# HV-Measurement.net
KiCad netlist of a schematic drawn in Altium Designer
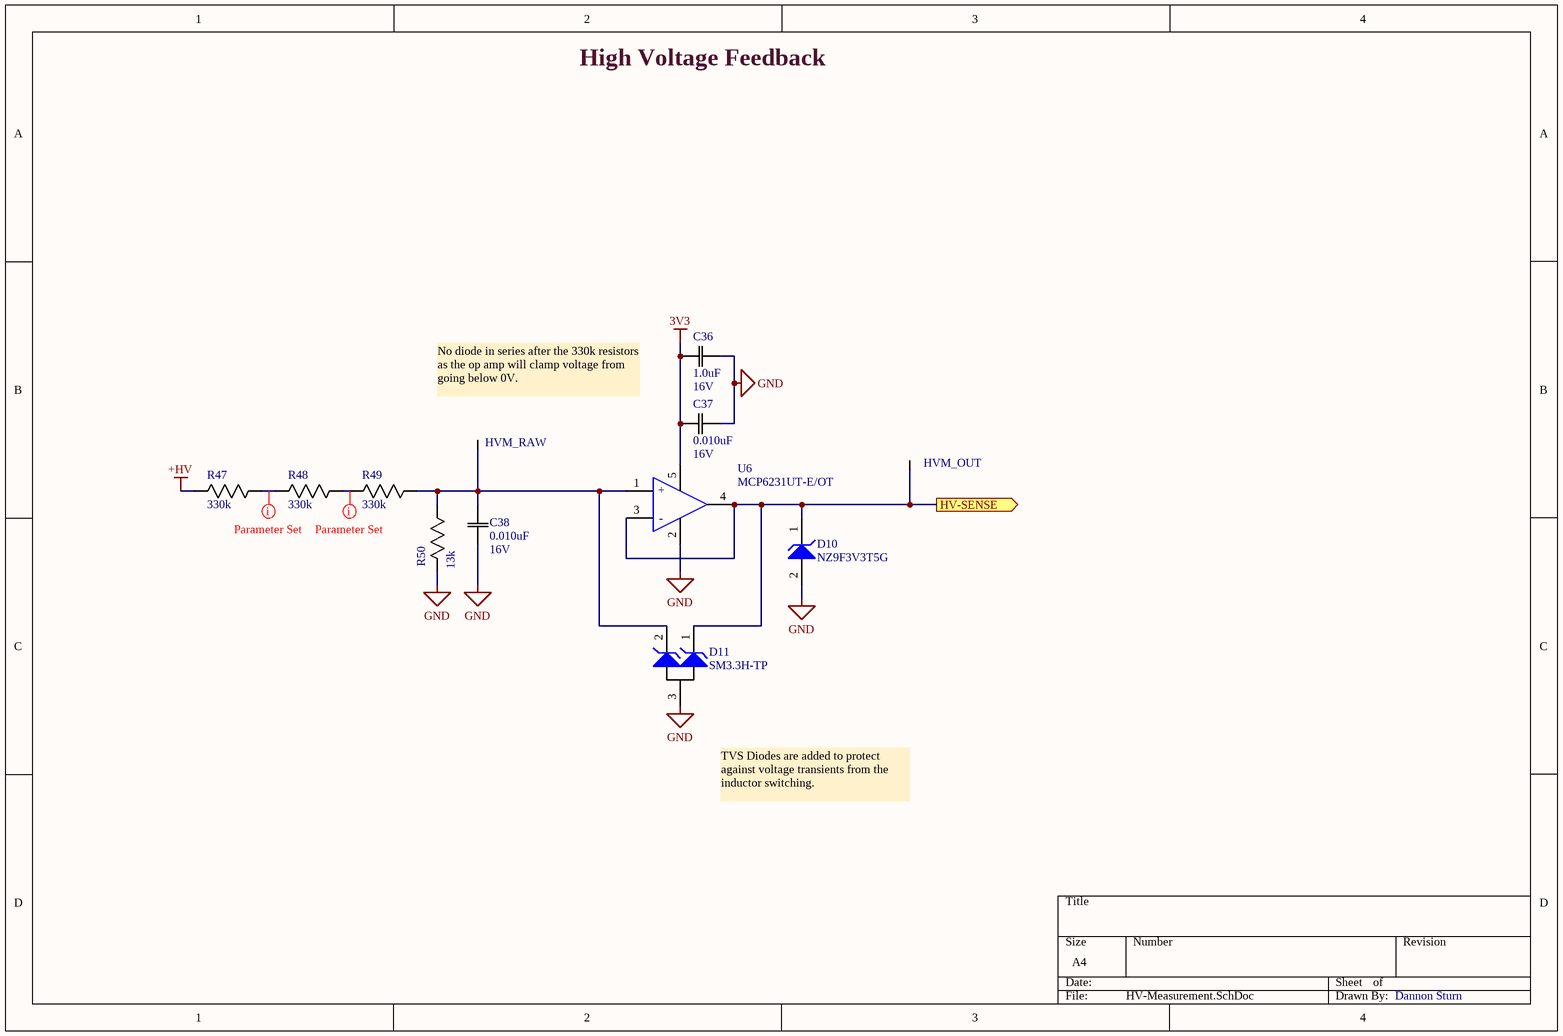
[diagram p0: HV-Measurement.SchDoc]

(export (version "E")
  (design (tool "Eeschema 10.0.6"))
  (components
    (comp (ref "C36")
      (value "1.0uF")
      (footprint "0603")
      (description "CAP CER 1.0UF 16V X5R 0603/0805")
      (fields
        (field (name "TOLERANCE") "10%")
        (field (name "RATING") "16V")
        (field (name "PART NUMBER") "CAP 1.0uF 16V")
      )
      (libsource (lib "capacitor_library") (part "CAP 1.0uF 16V"))
    )
    (comp (ref "C37")
      (value "0.010uF")
      (footprint "0603")
      (description "CAP CER 0.010UF 16V X5R 0603")
      (fields
        (field (name "TOLERANCE") "10%")
        (field (name "RATING") "16V")
        (field (name "PART NUMBER") "CAP 0.010uF 16V")
      )
      (libsource (lib "capacitor_library") (part "CAP 0.010uF 16V"))
    )
    (comp (ref "C38")
      (value "0.010uF")
      (footprint "0603")
      (description "CAP CER 0.010UF 16V X5R 0603")
      (fields
        (field (name "TOLERANCE") "10%")
        (field (name "RATING") "16V")
        (field (name "PART NUMBER") "CAP 0.010uF 16V")
      )
      (libsource (lib "capacitor_library") (part "CAP 0.010uF 16V"))
    )
    (comp (ref "D10")
      (value "NZ9F3V3T5G")
      (footprint "SOD-923_0P6X0P85_ONS")
      (description "Zener Diode 3.3 V 200 mW ±5% Surface Mount SOD-923")
      (fields
        (field (name "PART NUMBER") "DIODE ZENER 3.3 200mW")
        (field (name "COPYRIGHT") "Copyright (C) 2021 Ultra Librarian. All rights reserved.")
      )
      (libsource (lib "Diode_Library") (part "DIODE ZENER 3.3 200mW"))
    )
    (comp (ref "D11")
      (value "SM3.3H-TP")
      (footprint "SOT-23A-3")
      (description "3.3V Reverese Standoff, 3.5V Breakdown, 12.5V Clamp 40A (8/20µs) Ipp Tvs Diode SMD SOT-23")
      (fields (field (name "PART NUMBER") "DIODE TVS 3.3VR 3.5VBR"))
      (libsource (lib "Diode_Library") (part "DIODE TVS 3.3VR 3.5VBR"))
    )
    (comp (ref "HVM_OUT")
      (value "Test Point (Via)")
      (footprint "TP")
      (libsource (lib "IC_Library") (part "Test Point (Via)"))
    )
    (comp (ref "HVM_RAW")
      (value "Test Point (Via)")
      (footprint "TP")
      (libsource (lib "IC_Library") (part "Test Point (Via)"))
    )
    (comp (ref "R47")
      (value "330k")
      (footprint "0603")
      (description "RES SMD 274K OHM 1% 1/8W 0603")
      (fields (field (name "PART NUMBER") "RES 330k 1/8W - 1%"))
      (libsource (lib "Resistor_Library") (part "RES 330k 1/8W - 1%"))
    )
    (comp (ref "R48")
      (value "330k")
      (footprint "0603")
      (description "RES SMD 274K OHM 1% 1/8W 0603")
      (fields (field (name "PART NUMBER") "RES 330k 1/8W - 1%"))
      (libsource (lib "Resistor_Library") (part "RES 330k 1/8W - 1%"))
    )
    (comp (ref "R49")
      (value "330k")
      (footprint "0603")
      (description "RES SMD 274K OHM 1% 1/8W 0603")
      (fields (field (name "PART NUMBER") "RES 330k 1/8W - 1%"))
      (libsource (lib "Resistor_Library") (part "RES 330k 1/8W - 1%"))
    )
    (comp (ref "R50")
      (value "13k")
      (footprint "0603")
      (description "RES SMD 13K OHM 5% 1/8W 0603")
      (fields (field (name "TOLERANCE") "5%") (field (name "PART NUMBER") "RES 13k 1/8W"))
      (libsource (lib "Resistor_Library") (part "RES 13k 1/8W"))
    )
    (comp (ref "U6")
      (value "MCP6231UT-E/OT")
      (footprint "SOT-23-5_MC_MCH-L")
      (fields
        (field (name "PART NUMBER") "OP AMP MCP6231UT-E_OT")
        (field (name "COPYRIGHT") "Copyright (C) 2021 Ultra Librarian. All rights reserved.")
      )
      (libsource (lib "IC_Library") (part "OP AMP MCP6231UT-E/OT"))
    )
  )
  (nets
    (net (code "1") (name "+HV") (class "Default")
      (node (ref "R47") (pin "2") (pinfunction "R2_2") (pintype "passive"))
    )
    (net (code "2") (name "/HV-SENSE") (class "Default")
      (node (ref "D10") (pin "1") (pinfunction "K_1") (pintype "passive"))
      (node (ref "D11") (pin "1") (pinfunction "1_1") (pintype "passive"))
      (node (ref "HVM_OUT") (pin "1") (pinfunction "1_1") (pintype "passive"))
      (node (ref "U6") (pin "3") (pinfunction "IN-_3") (pintype "tri_state"))
      (node (ref "U6") (pin "4") (pinfunction "OUT_4") (pintype "passive"))
    )
    (net (code "3") (name "3V3") (class "Default")
      (node (ref "C36") (pin "2") (pinfunction "C2_2") (pintype "passive"))
      (node (ref "C37") (pin "1") (pinfunction "C1_1") (pintype "passive"))
      (node (ref "U6") (pin "5") (pinfunction "V+_5") (pintype "power_in"))
    )
    (net (code "4") (name "GND") (class "Default")
      (node (ref "C36") (pin "1") (pinfunction "C1_1") (pintype "passive"))
      (node (ref "C37") (pin "2") (pinfunction "C2_2") (pintype "passive"))
      (node (ref "C38") (pin "1") (pinfunction "C1_1") (pintype "passive"))
      (node (ref "D10") (pin "2") (pinfunction "A_2") (pintype "passive"))
      (node (ref "D11") (pin "3") (pinfunction "3_3") (pintype "passive"))
      (node (ref "R50") (pin "2") (pinfunction "R2_2") (pintype "passive"))
      (node (ref "U6") (pin "2") (pinfunction "V-_2") (pintype "power_in"))
    )
    (net (code "5") (name "Net-(C38-C2)") (class "Default")
      (node (ref "C38") (pin "2") (pinfunction "C2_2") (pintype "passive"))
      (node (ref "D11") (pin "2") (pinfunction "2_2") (pintype "passive"))
      (node (ref "HVM_RAW") (pin "1") (pinfunction "1_1") (pintype "passive"))
      (node (ref "R49") (pin "1") (pinfunction "R1_1") (pintype "passive"))
      (node (ref "R50") (pin "1") (pinfunction "R1_1") (pintype "passive"))
      (node (ref "U6") (pin "1") (pinfunction "IN+_1") (pintype "tri_state"))
    )
    (net (code "6") (name "Net-(R47-R1)") (class "Default")
      (node (ref "R47") (pin "1") (pinfunction "R1_1") (pintype "passive"))
      (node (ref "R48") (pin "2") (pinfunction "R2_2") (pintype "passive"))
    )
    (net (code "7") (name "Net-(R48-R1)") (class "Default")
      (node (ref "R48") (pin "1") (pinfunction "R1_1") (pintype "passive"))
      (node (ref "R49") (pin "2") (pinfunction "R2_2") (pintype "passive"))
    )
  )
)
